# Power.net
KiCad netlist of a schematic drawn in Altium Designer
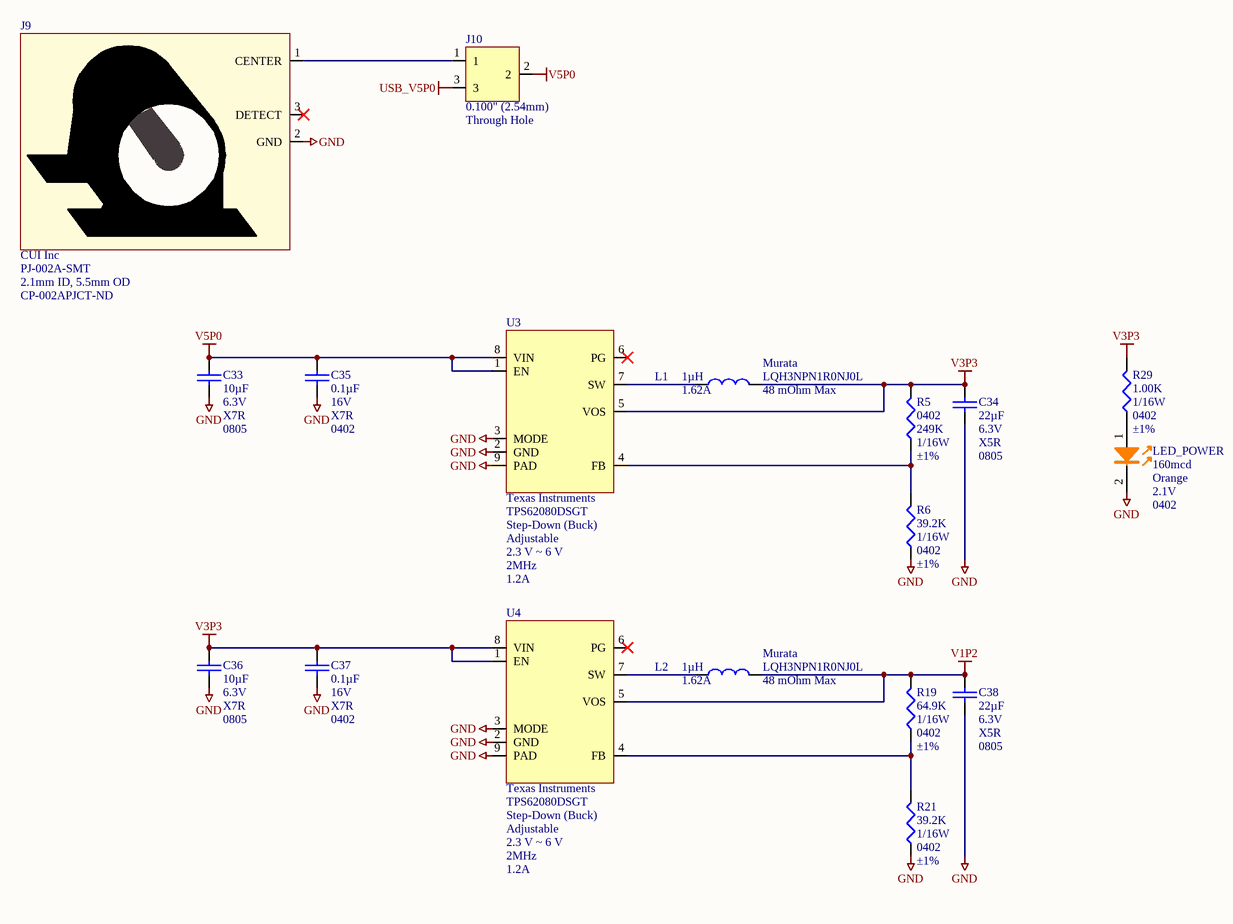
[diagram p0: Power.SchDoc]

(export (version "E")
  (design (tool "Eeschema 10.0.6"))
  (components
    (comp (ref "C33")
      (value "10uF")
      (footprint "C_ERA-0805")
      (description "CAP CER 10UF 6.3V X7R 10% 0805")
      (fields
        (field (name "MANUFACTURER") "Taiyo Yuden")
        (field (name "MANUFACTURER PART NUMBER") "JMK212BJ106KD-T")
        (field (name "CAPACITANCE") "10µF")
        (field (name "VOLTAGE - RATED") "6.3V")
        (field (name "TEMPERATURE COEFFICIENT") "X7R")
        (field (name "PACKAGE / CASE") "0805")
      )
      (libsource (lib "Main LibraryX") (part "C_0805_10UF_6.3V"))
    )
    (comp (ref "C34")
      (value "22uF")
      (footprint "C_ERA-0805")
      (description "CAP CER 22UF 6.3V X7R 10% 0805")
      (fields
        (field (name "MANUFACTURER") "AVX Corporation")
        (field (name "MANUFACTURER PART NUMBER") "08056D226MAT2A")
        (field (name "CAPACITANCE") "22µF")
        (field (name "VOLTAGE - RATED") "6.3V")
        (field (name "TEMPERATURE COEFFICIENT") "X5R")
        (field (name "PACKAGE / CASE") "0805")
      )
      (libsource (lib "Main LibraryX") (part "C_0805_22UF_6.3V"))
    )
    (comp (ref "C35")
      (value "0.1uF")
      (footprint "C_ERA-0402")
      (description "CAP CER .10UF 16V X7R 0402")
      (fields
        (field (name "MANUFACTURER") "TDK Corporation")
        (field (name "MANUFACTURER PART NUMBER") "C1005X7R1C104K")
        (field (name "CAPACITANCE") "0.1µF")
        (field (name "VOLTAGE - RATED") "16V")
        (field (name "TEMPERATURE COEFFICIENT") "X7R")
        (field (name "PACKAGE / CASE") "0402")
      )
      (libsource (lib "Main LibraryX") (part "C_0402_0.1UF_16V"))
    )
    (comp (ref "C36")
      (value "10uF")
      (footprint "C_ERA-0805")
      (description "CAP CER 10UF 6.3V X7R 10% 0805")
      (fields
        (field (name "MANUFACTURER") "Taiyo Yuden")
        (field (name "MANUFACTURER PART NUMBER") "JMK212BJ106KD-T")
        (field (name "CAPACITANCE") "10µF")
        (field (name "VOLTAGE - RATED") "6.3V")
        (field (name "TEMPERATURE COEFFICIENT") "X7R")
        (field (name "PACKAGE / CASE") "0805")
      )
      (libsource (lib "Main LibraryX") (part "C_0805_10UF_6.3V"))
    )
    (comp (ref "C37")
      (value "0.1uF")
      (footprint "C_ERA-0402")
      (description "CAP CER .10UF 16V X7R 0402")
      (fields
        (field (name "MANUFACTURER") "TDK Corporation")
        (field (name "MANUFACTURER PART NUMBER") "C1005X7R1C104K")
        (field (name "CAPACITANCE") "0.1µF")
        (field (name "VOLTAGE - RATED") "16V")
        (field (name "TEMPERATURE COEFFICIENT") "X7R")
        (field (name "PACKAGE / CASE") "0402")
      )
      (libsource (lib "Main LibraryX") (part "C_0402_0.1UF_16V"))
    )
    (comp (ref "C38")
      (value "22uF")
      (footprint "C_ERA-0805")
      (description "CAP CER 22UF 6.3V X7R 10% 0805")
      (fields
        (field (name "MANUFACTURER") "AVX Corporation")
        (field (name "MANUFACTURER PART NUMBER") "08056D226MAT2A")
        (field (name "CAPACITANCE") "22µF")
        (field (name "VOLTAGE - RATED") "6.3V")
        (field (name "TEMPERATURE COEFFICIENT") "X5R")
        (field (name "PACKAGE / CASE") "0805")
      )
      (libsource (lib "Main LibraryX") (part "C_0805_22UF_6.3V"))
    )
    (comp (ref "J9")
      (value "Barrel Jack")
      (footprint "PJ-002BH-SMT")
      (description "CONN POWER JACK 2.1X5.5MM SMD")
      (fields
        (field (name "MANUFACTURER") "CUI Inc")
        (field (name "MANUFACTURER PART NUMBER") "PJ-002A-SMT")
        (field (name "PLUG/MATING PLUG DIAMETER") "2.1mm ID, 5.5mm OD")
        (field (name "SUPPLIER PART NUMBER 1") "CP-002APJCT-ND")
      )
      (libsource (lib "Main LibraryX") (part "J_BARREL_JACK_2.1"))
    )
    (comp (ref "J10")
      (value "J_HDR1X3_JUMPER_SELECT")
      (footprint "HDR_1X3")
      (description "CONN HEADER .100\" 3POS TIN PCB")
      (fields
        (field (name "MANUFACTURER") "Samtec")
        (field (name "MANUFACTURER PART NUMBER") "TSW-103-07-T-S")
        (field (name "PITCH") "0.100\" (2.54mm)")
        (field (name "MOUNTING TYPE") "Through Hole")
      )
      (libsource (lib "Main LibraryX") (part "J_HDR1X3_JUMPER_SELECT"))
    )
    (comp (ref "L1")
      (value "1.0uH")
      (footprint "INDNRH1212")
      (description "INDUCTOR POWER 1.0UH 1620MA 1212")
      (fields
        (field (name "TOLERANCE") "±30%")
        (field (name "MANUFACTURER PART NUMBER") "LQH3NPN1R0NJ0L")
        (field (name "INDUCTANCE") "1µH")
        (field (name "CURRENT") "1.62A")
        (field (name "DC RESISTANCE (DCR)") "48 mOhm Max")
        (field (name "MANUFACTURER") "Murata")
      )
      (libsource (lib "Main Library") (part "L_1.0UH_1.62A"))
    )
    (comp (ref "L2")
      (value "1.0uH")
      (footprint "INDNRH1212")
      (description "INDUCTOR POWER 1.0UH 1620MA 1212")
      (fields
        (field (name "TOLERANCE") "±30%")
        (field (name "MANUFACTURER PART NUMBER") "LQH3NPN1R0NJ0L")
        (field (name "INDUCTANCE") "1µH")
        (field (name "CURRENT") "1.62A")
        (field (name "DC RESISTANCE (DCR)") "48 mOhm Max")
        (field (name "MANUFACTURER") "Murata")
      )
      (libsource (lib "Main Library") (part "L_1.0UH_1.62A"))
    )
    (comp (ref "LED_POWER")
      (value "LED_ORN_0402")
      (footprint "DIOM1005X07L_ORANGE")
      (description "LED 1X0.5MM 601NM ORN WTRCLR SMD")
      (fields
        (field (name "MANUFACTURER") "Kingbright Corp")
        (field (name "MANUFACTURER PART NUMBER") "APHHS1005SECK")
        (field (name "MILLICANDELA RATING") "160mcd")
        (field (name "COLOR") "Orange")
        (field (name "VOLTAGE - FORWARD (VF) TYP") "2.1V")
        (field (name "PACKAGE / CASE") "0402")
      )
      (libsource (lib "Main Library") (part "LED_ORN_0402"))
    )
    (comp (ref "R5")
      (value "R_0402_249K")
      (footprint "ERA-0402")
      (description "RES 249K OHM 1/16W 1% 0402 SMD")
      (fields
        (field (name "MANUFACTURER") "Yageo")
        (field (name "MANUFACTURER PART NUMBER") "RC0402FR-07249KL")
        (field (name "PACKAGE / CASE") "0402")
        (field (name "RESISTANCE (OHMS)") "249K")
        (field (name "POWER (WATTS)") "1/16W")
        (field (name "TOLERANCE") "±1%")
      )
      (libsource (lib "Main LibraryX") (part "R_0402_249K"))
    )
    (comp (ref "R6")
      (value "R_0402_39.2K")
      (footprint "ERA-0402")
      (description "RES 39.2K OHM 1/16W 1% 0402 SMD")
      (fields
        (field (name "RESISTANCE IN OHMS") "39.2K")
        (field (name "POWER (WATTS)") "1/16W")
        (field (name "CASE") "0402")
        (field (name "TOLERANCE") "±1%")
        (field (name "MANUFACTURER") "Yageo")
        (field (name "MANUFACTURER PART NUMBER") "RC0402FR-0739K2L")
      )
      (libsource (lib "Main LibraryX") (part "R_0402_39.2K"))
    )
    (comp (ref "R19")
      (value "R_0402_64.9K")
      (footprint "ERA-0402")
      (description "RES 64.9K OHM 1/16W 1% 0402 SMD")
      (fields
        (field (name "MANUFACTURER") "Yageo")
        (field (name "MANUFACTURER PART NUMBER") "RC0402FR-0764K9L")
        (field (name "RESISTANCE IN OHMS") "64.9K")
        (field (name "POWER (WATTS)") "1/16W")
        (field (name "CASE") "0402")
        (field (name "TOLERANCE") "±1%")
      )
      (libsource (lib "Main Library") (part "R_0402_64.9K"))
    )
    (comp (ref "R21")
      (value "R_0402_39.2K")
      (footprint "ERA-0402")
      (description "RES 39.2K OHM 1/16W 1% 0402 SMD")
      (fields
        (field (name "RESISTANCE IN OHMS") "39.2K")
        (field (name "POWER (WATTS)") "1/16W")
        (field (name "CASE") "0402")
        (field (name "TOLERANCE") "±1%")
        (field (name "MANUFACTURER") "Yageo")
        (field (name "MANUFACTURER PART NUMBER") "RC0402FR-0739K2L")
      )
      (libsource (lib "Main LibraryX") (part "R_0402_39.2K"))
    )
    (comp (ref "R29")
      (value "1.0k Ohms")
      (footprint "ERA-0402")
      (description "RES 1.00K OHM 1/16W 1% 0402 SMD")
      (fields
        (field (name "MANUFACTURER") "Yageo")
        (field (name "MANUFACTURER PART NUMBER") "RC0402FR-071KL")
        (field (name "RESISTANCE IN OHMS") "1.00K")
        (field (name "POWER (WATTS)") "1/16W")
        (field (name "CASE") "0402")
        (field (name "TOLERANCE") "±1%")
      )
      (libsource (lib "Main Library") (part "R_0402_1.0K"))
    )
    (comp (ref "U3")
      (value "TPS62080")
      (footprint "QFN50P200X200X80-8L")
      (description "IC BUCK SYNC ADJ 1.2A 8WSON")
      (fields
        (field (name "MANUFACTURER") "Texas Instruments")
        (field (name "MANUFACTURER PART NUMBER") "TPS62080DSGT")
        (field (name "TYPE") "Step-Down (Buck)")
        (field (name "OUTPUT TYPE") "Adjustable")
        (field (name "VOLTAGE - INPUT") "2.3 V ~ 6 V")
        (field (name "FREQUENCY - SWITCHING") "2MHz")
        (field (name "CURRENT - OUTPUT") "1.2A")
      )
      (libsource (lib "Main Library") (part "U_TPS62080"))
    )
    (comp (ref "U4")
      (value "TPS62080")
      (footprint "QFN50P200X200X80-8L")
      (description "IC BUCK SYNC ADJ 1.2A 8WSON")
      (fields
        (field (name "MANUFACTURER") "Texas Instruments")
        (field (name "MANUFACTURER PART NUMBER") "TPS62080DSGT")
        (field (name "TYPE") "Step-Down (Buck)")
        (field (name "OUTPUT TYPE") "Adjustable")
        (field (name "VOLTAGE - INPUT") "2.3 V ~ 6 V")
        (field (name "FREQUENCY - SWITCHING") "2MHz")
        (field (name "CURRENT - OUTPUT") "1.2A")
      )
      (libsource (lib "Main Library") (part "U_TPS62080"))
    )
  )
  (nets
    (net (code "1") (name "GND") (class "Default")
      (node (ref "C33") (pin "1") (pinfunction "1_1") (pintype "passive"))
      (node (ref "C34") (pin "1") (pinfunction "1_1") (pintype "passive"))
      (node (ref "C35") (pin "1") (pinfunction "1_1") (pintype "passive"))
      (node (ref "C36") (pin "1") (pinfunction "1_1") (pintype "passive"))
      (node (ref "C37") (pin "1") (pinfunction "1_1") (pintype "passive"))
      (node (ref "C38") (pin "1") (pinfunction "1_1") (pintype "passive"))
      (node (ref "J9") (pin "2") (pinfunction "GND_2") (pintype "passive"))
      (node (ref "LED_POWER") (pin "2") (pinfunction "2_2") (pintype "passive"))
      (node (ref "R21") (pin "2") (pinfunction "2_2") (pintype "passive"))
      (node (ref "R6") (pin "2") (pinfunction "2_2") (pintype "passive"))
      (node (ref "U3") (pin "2") (pinfunction "GND_2") (pintype "passive"))
      (node (ref "U3") (pin "3") (pinfunction "MODE_3") (pintype "passive"))
      (node (ref "U3") (pin "9") (pinfunction "PAD_9") (pintype "passive"))
      (node (ref "U4") (pin "2") (pinfunction "GND_2") (pintype "passive"))
      (node (ref "U4") (pin "3") (pinfunction "MODE_3") (pintype "passive"))
      (node (ref "U4") (pin "9") (pinfunction "PAD_9") (pintype "passive"))
    )
    (net (code "2") (name "Net-(J9-CENTER)") (class "Default")
      (node (ref "J10") (pin "1") (pinfunction "1_1") (pintype "passive"))
      (node (ref "J9") (pin "1") (pinfunction "CENTER_1") (pintype "passive"))
    )
    (net (code "3") (name "Net-(LED_POWER-Pad1)") (class "Default")
      (node (ref "LED_POWER") (pin "1") (pinfunction "1_1") (pintype "passive"))
      (node (ref "R29") (pin "2") (pinfunction "2_2") (pintype "passive"))
    )
    (net (code "4") (name "Net-(U3-FB)") (class "Default")
      (node (ref "R5") (pin "2") (pinfunction "2_2") (pintype "passive"))
      (node (ref "R6") (pin "1") (pinfunction "1_1") (pintype "passive"))
      (node (ref "U3") (pin "4") (pinfunction "FB_4") (pintype "passive"))
    )
    (net (code "5") (name "Net-(U3-SW)") (class "Default")
      (node (ref "L1") (pin "1") (pintype "passive"))
      (node (ref "U3") (pin "7") (pinfunction "SW_7") (pintype "passive"))
    )
    (net (code "6") (name "Net-(U4-FB)") (class "Default")
      (node (ref "R19") (pin "2") (pinfunction "2_2") (pintype "passive"))
      (node (ref "R21") (pin "1") (pinfunction "1_1") (pintype "passive"))
      (node (ref "U4") (pin "4") (pinfunction "FB_4") (pintype "passive"))
    )
    (net (code "7") (name "Net-(U4-SW)") (class "Default")
      (node (ref "L2") (pin "1") (pintype "passive"))
      (node (ref "U4") (pin "7") (pinfunction "SW_7") (pintype "passive"))
    )
    (net (code "8") (name "USB_V5P0") (class "Default")
      (node (ref "J10") (pin "3") (pinfunction "3_3") (pintype "passive"))
    )
    (net (code "9") (name "V1P2") (class "Default")
      (node (ref "C38") (pin "2") (pinfunction "2_2") (pintype "passive"))
      (node (ref "L2") (pin "2") (pintype "passive"))
      (node (ref "R19") (pin "1") (pinfunction "1_1") (pintype "passive"))
      (node (ref "U4") (pin "5") (pinfunction "VOS_5") (pintype "passive"))
    )
    (net (code "10") (name "V3P3") (class "Default")
      (node (ref "C34") (pin "2") (pinfunction "2_2") (pintype "passive"))
      (node (ref "C36") (pin "2") (pinfunction "2_2") (pintype "passive"))
      (node (ref "C37") (pin "2") (pinfunction "2_2") (pintype "passive"))
      (node (ref "L1") (pin "2") (pintype "passive"))
      (node (ref "R29") (pin "1") (pinfunction "1_1") (pintype "passive"))
      (node (ref "R5") (pin "1") (pinfunction "1_1") (pintype "passive"))
      (node (ref "U3") (pin "5") (pinfunction "VOS_5") (pintype "passive"))
      (node (ref "U4") (pin "1") (pinfunction "EN_1") (pintype "passive"))
      (node (ref "U4") (pin "8") (pinfunction "VIN_8") (pintype "passive"))
    )
    (net (code "11") (name "V5P0") (class "Default")
      (node (ref "C33") (pin "2") (pinfunction "2_2") (pintype "passive"))
      (node (ref "C35") (pin "2") (pinfunction "2_2") (pintype "passive"))
      (node (ref "J10") (pin "2") (pinfunction "2_2") (pintype "passive"))
      (node (ref "U3") (pin "1") (pinfunction "EN_1") (pintype "passive"))
      (node (ref "U3") (pin "8") (pinfunction "VIN_8") (pintype "passive"))
    )
    (net (code "12") (name "unconnected-(J9-DETECT-Pad3)") (class "Default")
      (node (ref "J9") (pin "3") (pinfunction "DETECT_3") (pintype "passive+no_connect"))
    )
    (net (code "13") (name "unconnected-(U3-PG-Pad6)") (class "Default")
      (node (ref "U3") (pin "6") (pinfunction "PG_6") (pintype "passive+no_connect"))
    )
    (net (code "14") (name "unconnected-(U4-PG-Pad6)") (class "Default")
      (node (ref "U4") (pin "6") (pinfunction "PG_6") (pintype "passive+no_connect"))
    )
  )
)
